# haptic_ring_prototype.net
KiCad netlist of a schematic drawn in Altium Designer
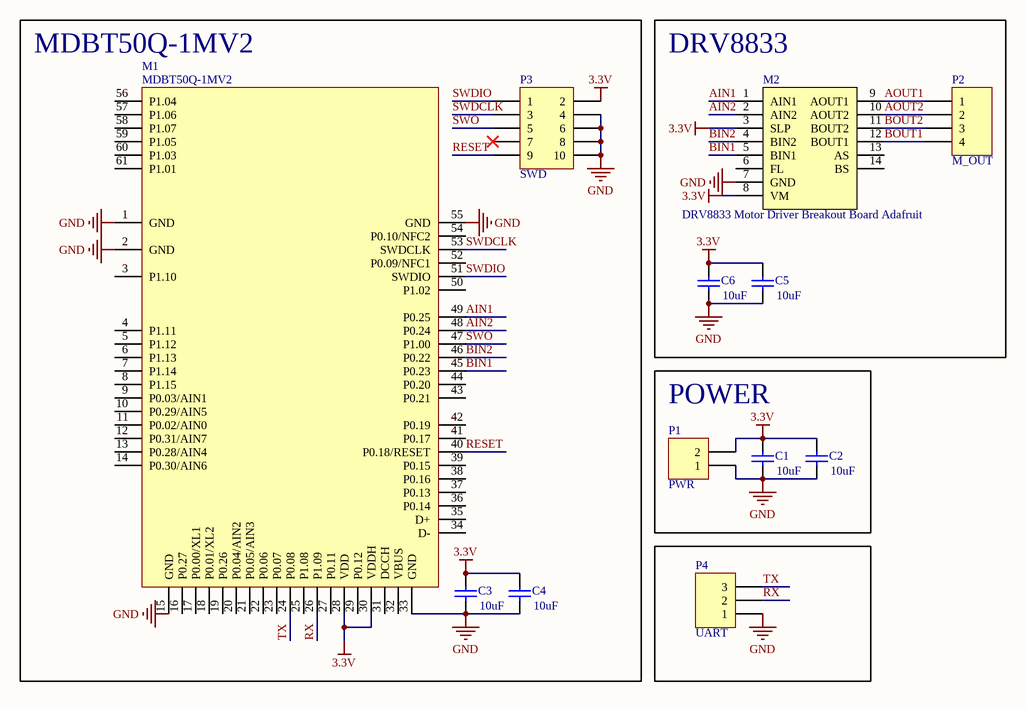
[diagram p0: haptic_ring_prototype.SchDoc]

(export (version "E")
  (design (tool "Eeschema 10.0.6"))
  (components
    (comp (ref "C1")
      (value "10uF")
      (footprint "C_0402")
      (description "Capacitor (Semiconductor SIM Model)")
      (fields (field (name "Comment") "Cap Semi") (field (name "PUBLISHER") "Altium Limited"))
      (libsource (lib "Miscellaneous Devices") (part "Cap Semi"))
    )
    (comp (ref "C2")
      (value "10uF")
      (footprint "C_0402")
      (description "Capacitor (Semiconductor SIM Model)")
      (fields (field (name "Comment") "Cap Semi") (field (name "PUBLISHER") "Altium Limited"))
      (libsource (lib "Miscellaneous Devices") (part "Cap Semi"))
    )
    (comp (ref "C3")
      (value "10uF")
      (footprint "C_0402")
      (description "Capacitor (Semiconductor SIM Model)")
      (fields (field (name "Comment") "Cap Semi") (field (name "PUBLISHER") "Altium Limited"))
      (libsource (lib "Miscellaneous Devices") (part "Cap Semi"))
    )
    (comp (ref "C4")
      (value "10uF")
      (footprint "C_0402")
      (description "Capacitor (Semiconductor SIM Model)")
      (fields (field (name "Comment") "Cap Semi") (field (name "PUBLISHER") "Altium Limited"))
      (libsource (lib "Miscellaneous Devices") (part "Cap Semi"))
    )
    (comp (ref "C5")
      (value "10uF")
      (footprint "C_0402")
      (description "Capacitor (Semiconductor SIM Model)")
      (fields (field (name "Comment") "Cap Semi") (field (name "PUBLISHER") "Altium Limited"))
      (libsource (lib "Miscellaneous Devices") (part "Cap Semi"))
    )
    (comp (ref "C6")
      (value "10uF")
      (footprint "C_0402")
      (description "Capacitor (Semiconductor SIM Model)")
      (fields (field (name "Comment") "Cap Semi") (field (name "PUBLISHER") "Altium Limited"))
      (libsource (lib "Miscellaneous Devices") (part "Cap Semi"))
    )
    (comp (ref "M1")
      (value "MDBT50Q-1MV2")
      (footprint "MDBT50Q-1MV2")
      (description "MDBT50Q_52840")
      (libsource (lib "My_lib") (part "MDBT50Q_52840"))
    )
    (comp (ref "M2")
      (value "DRV8833 Motor Driver Breakout Board Adafruit")
      (footprint "DRV8833 DC/Stepper Motor Driver Breakout Board Adafruit")
      (libsource (lib "My_lib") (part "DRV8833 DC/Stepper Motor Driver Breakout Board Adafruit"))
    )
    (comp (ref "P1")
      (value "PWR")
      (footprint "HDR1X2")
      (description "Header, 2-Pin")
      (fields (field (name "PUBLISHER") "Altium Limited"))
      (libsource (lib "Miscellaneous Connectors") (part "Header 2"))
    )
    (comp (ref "P2")
      (value "M_OUT")
      (footprint "HDR1X4")
      (description "Header, 4-Pin")
      (fields (field (name "PUBLISHER") "Altium Limited"))
      (libsource (lib "Miscellaneous Connectors") (part "Header 4"))
    )
    (comp (ref "P3")
      (value "SWD")
      (footprint "header male th 1.27 5x2 pins")
      (description "Header, 5-Pin, Dual row")
      (fields (field (name "PUBLISHER") "Altium Limited"))
      (libsource (lib "Miscellaneous Connectors") (part "Header 5X2"))
    )
    (comp (ref "P4")
      (value "UART")
      (footprint "HDR1X3")
      (description "Header, 3-Pin")
      (fields (field (name "PUBLISHER") "Altium Limited"))
      (libsource (lib "Miscellaneous Connectors") (part "Header 3"))
    )
  )
  (nets
    (net (code "1") (name "/AIN1") (class "Default")
      (node (ref "M1") (pin "49") (pinfunction "P0.25_49") (pintype "passive"))
      (node (ref "M2") (pin "1") (pinfunction "AIN1_1") (pintype "passive"))
    )
    (net (code "2") (name "/AIN2") (class "Default")
      (node (ref "M1") (pin "48") (pinfunction "P0.24_48") (pintype "passive"))
      (node (ref "M2") (pin "2") (pinfunction "AIN2_2") (pintype "passive"))
    )
    (net (code "3") (name "/AOUT1") (class "Default")
      (node (ref "M2") (pin "9") (pinfunction "AOUT1_9") (pintype "passive"))
      (node (ref "P2") (pin "1") (pinfunction "1_1") (pintype "passive"))
    )
    (net (code "4") (name "/AOUT2") (class "Default")
      (node (ref "M2") (pin "10") (pinfunction "AOUT2_10") (pintype "passive"))
      (node (ref "P2") (pin "2") (pinfunction "2_2") (pintype "passive"))
    )
    (net (code "5") (name "/BIN1") (class "Default")
      (node (ref "M1") (pin "45") (pinfunction "P0.23_45") (pintype "passive"))
      (node (ref "M2") (pin "5") (pinfunction "BIN1_5") (pintype "passive"))
    )
    (net (code "6") (name "/BIN2") (class "Default")
      (node (ref "M1") (pin "46") (pinfunction "P0.22_46") (pintype "passive"))
      (node (ref "M2") (pin "4") (pinfunction "BIN2_4") (pintype "passive"))
    )
    (net (code "7") (name "/BOUT1") (class "Default")
      (node (ref "M2") (pin "12") (pinfunction "BOUT1_12") (pintype "passive"))
      (node (ref "P2") (pin "4") (pinfunction "4_4") (pintype "passive"))
    )
    (net (code "8") (name "/BOUT2") (class "Default")
      (node (ref "M2") (pin "11") (pinfunction "BOUT2_11") (pintype "passive"))
      (node (ref "P2") (pin "3") (pinfunction "3_3") (pintype "passive"))
    )
    (net (code "9") (name "/RESET") (class "Default")
      (node (ref "M1") (pin "40") (pinfunction "P0.18/RESET_40") (pintype "passive"))
      (node (ref "P3") (pin "9") (pinfunction "9_9") (pintype "passive"))
    )
    (net (code "10") (name "/RX") (class "Default")
      (node (ref "M1") (pin "26") (pinfunction "P1.09_26") (pintype "passive"))
      (node (ref "P4") (pin "2") (pinfunction "2_2") (pintype "passive"))
    )
    (net (code "11") (name "/SWDCLK") (class "Default")
      (node (ref "M1") (pin "53") (pinfunction "SWDCLK_53") (pintype "passive"))
      (node (ref "P3") (pin "3") (pinfunction "3_3") (pintype "passive"))
    )
    (net (code "12") (name "/SWDIO") (class "Default")
      (node (ref "M1") (pin "51") (pinfunction "SWDIO_51") (pintype "passive"))
      (node (ref "P3") (pin "1") (pinfunction "1_1") (pintype "passive"))
    )
    (net (code "13") (name "/SWO") (class "Default")
      (node (ref "M1") (pin "47") (pinfunction "P1.00_47") (pintype "passive"))
      (node (ref "P3") (pin "5") (pinfunction "5_5") (pintype "passive"))
    )
    (net (code "14") (name "/TX") (class "Default")
      (node (ref "M1") (pin "24") (pinfunction "P0.08_24") (pintype "passive"))
      (node (ref "P4") (pin "3") (pinfunction "3_3") (pintype "passive"))
    )
    (net (code "15") (name "3.3V") (class "Default")
      (node (ref "C1") (pin "2") (pinfunction "2_2") (pintype "passive"))
      (node (ref "C2") (pin "2") (pinfunction "2_2") (pintype "passive"))
      (node (ref "C3") (pin "2") (pinfunction "2_2") (pintype "passive"))
      (node (ref "C4") (pin "2") (pinfunction "2_2") (pintype "passive"))
      (node (ref "C5") (pin "2") (pinfunction "2_2") (pintype "passive"))
      (node (ref "C6") (pin "2") (pinfunction "2_2") (pintype "passive"))
      (node (ref "M1") (pin "28") (pinfunction "VDD_28") (pintype "passive"))
      (node (ref "M1") (pin "30") (pinfunction "VDDH_30") (pintype "passive"))
      (node (ref "M2") (pin "3") (pinfunction "SLP_3") (pintype "passive"))
      (node (ref "M2") (pin "8") (pinfunction "VM_8") (pintype "passive"))
      (node (ref "P1") (pin "2") (pinfunction "2_2") (pintype "passive"))
      (node (ref "P3") (pin "2") (pinfunction "2_2") (pintype "passive"))
    )
    (net (code "16") (name "GND") (class "Default")
      (node (ref "C1") (pin "1") (pinfunction "1_1") (pintype "passive"))
      (node (ref "C2") (pin "1") (pinfunction "1_1") (pintype "passive"))
      (node (ref "C3") (pin "1") (pinfunction "1_1") (pintype "passive"))
      (node (ref "C4") (pin "1") (pinfunction "1_1") (pintype "passive"))
      (node (ref "C5") (pin "1") (pinfunction "1_1") (pintype "passive"))
      (node (ref "C6") (pin "1") (pinfunction "1_1") (pintype "passive"))
      (node (ref "M1") (pin "1") (pinfunction "GND_1") (pintype "passive"))
      (node (ref "M1") (pin "15") (pinfunction "GND_15") (pintype "passive"))
      (node (ref "M1") (pin "2") (pinfunction "GND_2") (pintype "passive"))
      (node (ref "M1") (pin "33") (pinfunction "GND_33") (pintype "passive"))
      (node (ref "M1") (pin "55") (pinfunction "GND_55") (pintype "passive"))
      (node (ref "M2") (pin "7") (pinfunction "GND_7") (pintype "passive"))
      (node (ref "P1") (pin "1") (pinfunction "1_1") (pintype "passive"))
      (node (ref "P3") (pin "10") (pinfunction "10_10") (pintype "passive"))
      (node (ref "P3") (pin "4") (pinfunction "4_4") (pintype "passive"))
      (node (ref "P3") (pin "6") (pinfunction "6_6") (pintype "passive"))
      (node (ref "P3") (pin "8") (pinfunction "8_8") (pintype "passive"))
      (node (ref "P4") (pin "1") (pinfunction "1_1") (pintype "passive"))
    )
    (net (code "17") (name "unconnected-(M1-D+-Pad35)") (class "Default")
      (node (ref "M1") (pin "35") (pinfunction "D+_35") (pintype "passive"))
    )
    (net (code "18") (name "unconnected-(M1-D--Pad34)") (class "Default")
      (node (ref "M1") (pin "34") (pinfunction "D-_34") (pintype "passive"))
    )
    (net (code "19") (name "unconnected-(M1-DCCH-Pad31)") (class "Default")
      (node (ref "M1") (pin "31") (pinfunction "DCCH_31") (pintype "passive"))
    )
    (net (code "20") (name "unconnected-(M1-P0.00{slash}XL1-Pad17)") (class "Default")
      (node (ref "M1") (pin "17") (pinfunction "P0.00/XL1_17") (pintype "passive"))
    )
    (net (code "21") (name "unconnected-(M1-P0.01{slash}XL2-Pad18)") (class "Default")
      (node (ref "M1") (pin "18") (pinfunction "P0.01/XL2_18") (pintype "passive"))
    )
    (net (code "22") (name "unconnected-(M1-P0.02{slash}AIN0-Pad11)") (class "Default")
      (node (ref "M1") (pin "11") (pinfunction "P0.02/AIN0_11") (pintype "passive"))
    )
    (net (code "23") (name "unconnected-(M1-P0.03{slash}AIN1-Pad9)") (class "Default")
      (node (ref "M1") (pin "9") (pinfunction "P0.03/AIN1_9") (pintype "passive"))
    )
    (net (code "24") (name "unconnected-(M1-P0.04{slash}AIN2-Pad20)") (class "Default")
      (node (ref "M1") (pin "20") (pinfunction "P0.04/AIN2_20") (pintype "passive"))
    )
    (net (code "25") (name "unconnected-(M1-P0.05{slash}AIN3-Pad21)") (class "Default")
      (node (ref "M1") (pin "21") (pinfunction "P0.05/AIN3_21") (pintype "passive"))
    )
    (net (code "26") (name "unconnected-(M1-P0.06-Pad22)") (class "Default")
      (node (ref "M1") (pin "22") (pinfunction "P0.06_22") (pintype "passive"))
    )
    (net (code "27") (name "unconnected-(M1-P0.07-Pad23)") (class "Default")
      (node (ref "M1") (pin "23") (pinfunction "P0.07_23") (pintype "passive"))
    )
    (net (code "28") (name "unconnected-(M1-P0.09{slash}NFC1-Pad52)") (class "Default")
      (node (ref "M1") (pin "52") (pinfunction "P0.09/NFC1_52") (pintype "passive"))
    )
    (net (code "29") (name "unconnected-(M1-P0.10{slash}NFC2-Pad54)") (class "Default")
      (node (ref "M1") (pin "54") (pinfunction "P0.10/NFC2_54") (pintype "passive"))
    )
    (net (code "30") (name "unconnected-(M1-P0.11-Pad27)") (class "Default")
      (node (ref "M1") (pin "27") (pinfunction "P0.11_27") (pintype "passive"))
    )
    (net (code "31") (name "unconnected-(M1-P0.12-Pad29)") (class "Default")
      (node (ref "M1") (pin "29") (pinfunction "P0.12_29") (pintype "passive"))
    )
    (net (code "32") (name "unconnected-(M1-P0.13-Pad37)") (class "Default")
      (node (ref "M1") (pin "37") (pinfunction "P0.13_37") (pintype "passive"))
    )
    (net (code "33") (name "unconnected-(M1-P0.14-Pad36)") (class "Default")
      (node (ref "M1") (pin "36") (pinfunction "P0.14_36") (pintype "passive"))
    )
    (net (code "34") (name "unconnected-(M1-P0.15-Pad39)") (class "Default")
      (node (ref "M1") (pin "39") (pinfunction "P0.15_39") (pintype "passive"))
    )
    (net (code "35") (name "unconnected-(M1-P0.16-Pad38)") (class "Default")
      (node (ref "M1") (pin "38") (pinfunction "P0.16_38") (pintype "passive"))
    )
    (net (code "36") (name "unconnected-(M1-P0.17-Pad41)") (class "Default")
      (node (ref "M1") (pin "41") (pinfunction "P0.17_41") (pintype "passive"))
    )
    (net (code "37") (name "unconnected-(M1-P0.19-Pad42)") (class "Default")
      (node (ref "M1") (pin "42") (pinfunction "P0.19_42") (pintype "passive"))
    )
    (net (code "38") (name "unconnected-(M1-P0.20-Pad44)") (class "Default")
      (node (ref "M1") (pin "44") (pinfunction "P0.20_44") (pintype "passive"))
    )
    (net (code "39") (name "unconnected-(M1-P0.21-Pad43)") (class "Default")
      (node (ref "M1") (pin "43") (pinfunction "P0.21_43") (pintype "passive"))
    )
    (net (code "40") (name "unconnected-(M1-P0.26-Pad19)") (class "Default")
      (node (ref "M1") (pin "19") (pinfunction "P0.26_19") (pintype "passive"))
    )
    (net (code "41") (name "unconnected-(M1-P0.27-Pad16)") (class "Default")
      (node (ref "M1") (pin "16") (pinfunction "P0.27_16") (pintype "passive"))
    )
    (net (code "42") (name "unconnected-(M1-P0.28{slash}AIN4-Pad13)") (class "Default")
      (node (ref "M1") (pin "13") (pinfunction "P0.28/AIN4_13") (pintype "passive"))
    )
    (net (code "43") (name "unconnected-(M1-P0.29{slash}AIN5-Pad10)") (class "Default")
      (node (ref "M1") (pin "10") (pinfunction "P0.29/AIN5_10") (pintype "passive"))
    )
    (net (code "44") (name "unconnected-(M1-P0.30{slash}AIN6-Pad14)") (class "Default")
      (node (ref "M1") (pin "14") (pinfunction "P0.30/AIN6_14") (pintype "passive"))
    )
    (net (code "45") (name "unconnected-(M1-P0.31{slash}AIN7-Pad12)") (class "Default")
      (node (ref "M1") (pin "12") (pinfunction "P0.31/AIN7_12") (pintype "passive"))
    )
    (net (code "46") (name "unconnected-(M1-P1.01-Pad61)") (class "Default")
      (node (ref "M1") (pin "61") (pinfunction "P1.01_61") (pintype "passive"))
    )
    (net (code "47") (name "unconnected-(M1-P1.02-Pad50)") (class "Default")
      (node (ref "M1") (pin "50") (pinfunction "P1.02_50") (pintype "passive"))
    )
    (net (code "48") (name "unconnected-(M1-P1.03-Pad60)") (class "Default")
      (node (ref "M1") (pin "60") (pinfunction "P1.03_60") (pintype "passive"))
    )
    (net (code "49") (name "unconnected-(M1-P1.04-Pad56)") (class "Default")
      (node (ref "M1") (pin "56") (pinfunction "P1.04_56") (pintype "passive"))
    )
    (net (code "50") (name "unconnected-(M1-P1.05-Pad59)") (class "Default")
      (node (ref "M1") (pin "59") (pinfunction "P1.05_59") (pintype "passive"))
    )
    (net (code "51") (name "unconnected-(M1-P1.06-Pad57)") (class "Default")
      (node (ref "M1") (pin "57") (pinfunction "P1.06_57") (pintype "passive"))
    )
    (net (code "52") (name "unconnected-(M1-P1.07-Pad58)") (class "Default")
      (node (ref "M1") (pin "58") (pinfunction "P1.07_58") (pintype "passive"))
    )
    (net (code "53") (name "unconnected-(M1-P1.08-Pad25)") (class "Default")
      (node (ref "M1") (pin "25") (pinfunction "P1.08_25") (pintype "passive"))
    )
    (net (code "54") (name "unconnected-(M1-P1.10-Pad3)") (class "Default")
      (node (ref "M1") (pin "3") (pinfunction "P1.10_3") (pintype "passive"))
    )
    (net (code "55") (name "unconnected-(M1-P1.11-Pad4)") (class "Default")
      (node (ref "M1") (pin "4") (pinfunction "P1.11_4") (pintype "passive"))
    )
    (net (code "56") (name "unconnected-(M1-P1.12-Pad5)") (class "Default")
      (node (ref "M1") (pin "5") (pinfunction "P1.12_5") (pintype "passive"))
    )
    (net (code "57") (name "unconnected-(M1-P1.13-Pad6)") (class "Default")
      (node (ref "M1") (pin "6") (pinfunction "P1.13_6") (pintype "passive"))
    )
    (net (code "58") (name "unconnected-(M1-P1.14-Pad7)") (class "Default")
      (node (ref "M1") (pin "7") (pinfunction "P1.14_7") (pintype "passive"))
    )
    (net (code "59") (name "unconnected-(M1-P1.15-Pad8)") (class "Default")
      (node (ref "M1") (pin "8") (pinfunction "P1.15_8") (pintype "passive"))
    )
    (net (code "60") (name "unconnected-(M1-VBUS-Pad32)") (class "Default")
      (node (ref "M1") (pin "32") (pinfunction "VBUS_32") (pintype "passive"))
    )
    (net (code "61") (name "unconnected-(M2-AS-Pad13)") (class "Default")
      (node (ref "M2") (pin "13") (pinfunction "AS_13") (pintype "passive"))
    )
    (net (code "62") (name "unconnected-(M2-BS-Pad14)") (class "Default")
      (node (ref "M2") (pin "14") (pinfunction "BS_14") (pintype "passive"))
    )
    (net (code "63") (name "unconnected-(M2-FL-Pad6)") (class "Default")
      (node (ref "M2") (pin "6") (pinfunction "FL_6") (pintype "passive"))
    )
    (net (code "64") (name "unconnected-(P3-Pad7)") (class "Default")
      (node (ref "P3") (pin "7") (pinfunction "7_7") (pintype "passive+no_connect"))
    )
  )
)
